# VU.net
KiCad netlist of a schematic drawn in EAGLE
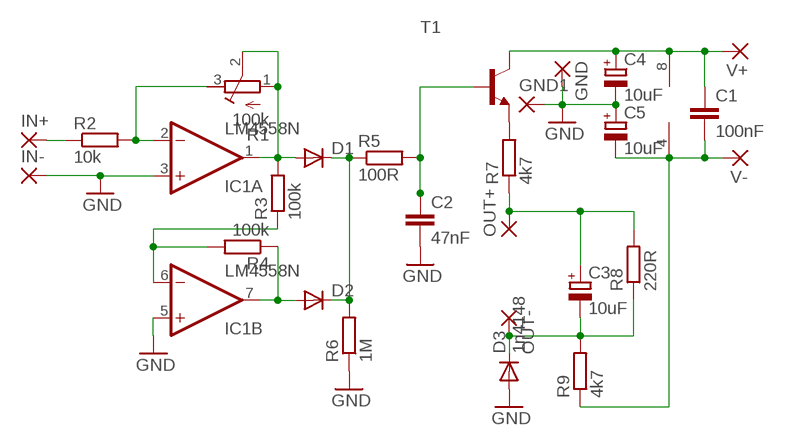
[diagram p0: schematic, sheet 1]

(export (version "E")
  (design (tool "Eeschema 10.0.6"))
  (components
    (comp (ref "C1")
      (value "100nF")
      (footprint "eagle-import:C050-025X075")
      (libsource (lib "eagle-import") (part "C-EU050-025X075"))
    )
    (comp (ref "C2")
      (value "47nF")
      (footprint "eagle-import:C050-025X075")
      (libsource (lib "eagle-import") (part "C-EU050-025X075"))
    )
    (comp (ref "C3")
      (value "10uF")
      (footprint "eagle-import:E2,5-5")
      (libsource (lib "eagle-import") (part "CPOL-EUE2.5-5"))
    )
    (comp (ref "C4")
      (value "10uF")
      (footprint "eagle-import:E2,5-5")
      (libsource (lib "eagle-import") (part "CPOL-EUE2.5-5"))
    )
    (comp (ref "C5")
      (value "10uF")
      (footprint "eagle-import:E2,5-5")
      (libsource (lib "eagle-import") (part "CPOL-EUE2.5-5"))
    )
    (comp (ref "D1")
      (value "DIODE-D-5")
      (footprint "eagle-import:D-5")
      (libsource (lib "eagle-import") (part "DIODE-D-5"))
    )
    (comp (ref "D2")
      (value "DIODE-D-5")
      (footprint "eagle-import:D-5")
      (libsource (lib "eagle-import") (part "DIODE-D-5"))
    )
    (comp (ref "D3")
      (value "1n4148")
      (footprint "eagle-import:D-5")
      (libsource (lib "eagle-import") (part "DIODE-D-5"))
    )
    (comp (ref "GND")
      (value "WIREPAD1,6/0,8")
      (footprint "eagle-import:1,6_0,8")
      (libsource (lib "eagle-import") (part "WIREPAD1,6/0,8"))
    )
    (comp (ref "GND1")
      (value "WIREPAD1,6/0,8")
      (footprint "eagle-import:1,6_0,8")
      (libsource (lib "eagle-import") (part "WIREPAD1,6/0,8"))
    )
    (comp (ref "IC1")
      (value "LM4558N")
      (footprint "eagle-import:DIL08")
      (libsource (lib "eagle-import") (part "4558NLM"))
    )
    (comp (ref "IN+")
      (value "WIREPAD1,6/0,8")
      (footprint "eagle-import:1,6_0,8")
      (libsource (lib "eagle-import") (part "WIREPAD1,6/0,8"))
    )
    (comp (ref "IN-")
      (value "WIREPAD1,6/0,8")
      (footprint "eagle-import:1,6_0,8")
      (libsource (lib "eagle-import") (part "WIREPAD1,6/0,8"))
    )
    (comp (ref "OUT+")
      (value "WIREPAD1,6/0,8")
      (footprint "eagle-import:1,6_0,8")
      (libsource (lib "eagle-import") (part "WIREPAD1,6/0,8"))
    )
    (comp (ref "OUT-")
      (value "WIREPAD1,6/0,8")
      (footprint "eagle-import:1,6_0,8")
      (libsource (lib "eagle-import") (part "WIREPAD1,6/0,8"))
    )
    (comp (ref "R1")
      (value "100k")
      (footprint "eagle-import:RTRIM64X")
      (libsource (lib "eagle-import") (part "R-TRIMM64X"))
    )
    (comp (ref "R2")
      (value "10k")
      (footprint "eagle-import:0207_7")
      (libsource (lib "eagle-import") (part "R-EU_0207/7"))
    )
    (comp (ref "R3")
      (value "100k")
      (footprint "eagle-import:0207_7")
      (libsource (lib "eagle-import") (part "R-EU_0207/7"))
    )
    (comp (ref "R4")
      (value "100k")
      (footprint "eagle-import:0207_2V")
      (libsource (lib "eagle-import") (part "R-EU_0207/2V"))
    )
    (comp (ref "R5")
      (value "100R")
      (footprint "eagle-import:0207_7")
      (libsource (lib "eagle-import") (part "R-EU_0207/7"))
    )
    (comp (ref "R6")
      (value "1M")
      (footprint "eagle-import:0207_7")
      (libsource (lib "eagle-import") (part "R-EU_0207/7"))
    )
    (comp (ref "R7")
      (value "4k7")
      (footprint "eagle-import:0207_7")
      (libsource (lib "eagle-import") (part "R-EU_0207/7"))
    )
    (comp (ref "R8")
      (value "220R")
      (footprint "eagle-import:0207_7")
      (libsource (lib "eagle-import") (part "R-EU_0207/7"))
    )
    (comp (ref "R9")
      (value "4k7")
      (footprint "eagle-import:0207_7")
      (libsource (lib "eagle-import") (part "R-EU_0207/7"))
    )
    (comp (ref "T1")
      (value "BC546-NPN-TO92-CBE")
      (footprint "eagle-import:TO92-CBE")
      (libsource (lib "eagle-import") (part "-NPN-TO92-CBEBC546"))
    )
    (comp (ref "V+")
      (value "WIREPAD1,6/0,8")
      (footprint "eagle-import:1,6_0,8")
      (libsource (lib "eagle-import") (part "WIREPAD1,6/0,8"))
    )
    (comp (ref "V-")
      (value "WIREPAD1,6/0,8")
      (footprint "eagle-import:1,6_0,8")
      (libsource (lib "eagle-import") (part "WIREPAD1,6/0,8"))
    )
  )
  (nets
    (net (code "1") (name "GND") (class "Default")
      (node (ref "C2") (pin "2") (pinfunction "2_2") (pintype "passive"))
      (node (ref "C4") (pin "-") (pinfunction "-_-") (pintype "passive"))
      (node (ref "C5") (pin "+") (pinfunction "+_+") (pintype "passive"))
      (node (ref "D3") (pin "A") (pinfunction "A_A") (pintype "passive"))
      (node (ref "GND") (pin "1") (pinfunction "P_1") (pintype "passive"))
      (node (ref "GND1") (pin "1") (pinfunction "P_1") (pintype "passive"))
      (node (ref "IC1") (pin "3") (pinfunction "+IN_3") (pintype "input"))
      (node (ref "IC1") (pin "5") (pinfunction "+IN_5") (pintype "input"))
      (node (ref "IN-") (pin "1") (pinfunction "P_1") (pintype "passive"))
      (node (ref "R6") (pin "1") (pinfunction "1_1") (pintype "passive"))
    )
    (net (code "2") (name "Net-(C2-Pad1)") (class "Default")
      (node (ref "C2") (pin "1") (pinfunction "1_1") (pintype "passive"))
      (node (ref "R5") (pin "2") (pinfunction "2_2") (pintype "passive"))
      (node (ref "T1") (pin "B") (pinfunction "B_B") (pintype "passive"))
    )
    (net (code "3") (name "Net-(D1-PadC)") (class "Default")
      (node (ref "D1") (pin "C") (pinfunction "C_C") (pintype "passive"))
      (node (ref "D2") (pin "C") (pinfunction "C_C") (pintype "passive"))
      (node (ref "R5") (pin "1") (pinfunction "1_1") (pintype "passive"))
      (node (ref "R6") (pin "2") (pinfunction "2_2") (pintype "passive"))
    )
    (net (code "4") (name "Net-(IC1A--IN)") (class "Default")
      (node (ref "IC1") (pin "2") (pinfunction "-IN_2") (pintype "input"))
      (node (ref "R1") (pin "3") (pinfunction "E_3") (pintype "passive"))
      (node (ref "R2") (pin "2") (pinfunction "2_2") (pintype "passive"))
    )
    (net (code "5") (name "Net-(IC1A-OUT)") (class "Default")
      (node (ref "D1") (pin "A") (pinfunction "A_A") (pintype "passive"))
      (node (ref "IC1") (pin "1") (pinfunction "OUT_1") (pintype "output"))
      (node (ref "R1") (pin "1") (pinfunction "A_1") (pintype "passive"))
      (node (ref "R1") (pin "2") (pinfunction "S_2") (pintype "passive"))
      (node (ref "R3") (pin "2") (pinfunction "2_2") (pintype "passive"))
    )
    (net (code "6") (name "Net-(IC1B--IN)") (class "Default")
      (node (ref "IC1") (pin "6") (pinfunction "-IN_6") (pintype "input"))
      (node (ref "R3") (pin "1") (pinfunction "1_1") (pintype "passive"))
      (node (ref "R4") (pin "2") (pinfunction "2_2") (pintype "passive"))
    )
    (net (code "7") (name "Net-(IC1B-OUT)") (class "Default")
      (node (ref "D2") (pin "A") (pinfunction "A_A") (pintype "passive"))
      (node (ref "IC1") (pin "7") (pinfunction "OUT_7") (pintype "output"))
      (node (ref "R4") (pin "1") (pinfunction "1_1") (pintype "passive"))
    )
    (net (code "8") (name "Net-(IC1C-V+)") (class "Default")
      (node (ref "C1") (pin "1") (pinfunction "1_1") (pintype "passive"))
      (node (ref "C4") (pin "+") (pinfunction "+_+") (pintype "passive"))
      (node (ref "IC1") (pin "8") (pinfunction "V+_8") (pintype "power_in"))
      (node (ref "T1") (pin "C") (pinfunction "C_C") (pintype "passive"))
      (node (ref "V+") (pin "1") (pinfunction "P_1") (pintype "passive"))
    )
    (net (code "9") (name "Net-(IC1C-V-)") (class "Default")
      (node (ref "C1") (pin "2") (pinfunction "2_2") (pintype "passive"))
      (node (ref "C5") (pin "-") (pinfunction "-_-") (pintype "passive"))
      (node (ref "IC1") (pin "4") (pinfunction "V-_4") (pintype "power_in"))
      (node (ref "R9") (pin "1") (pinfunction "1_1") (pintype "passive"))
      (node (ref "V-") (pin "1") (pinfunction "P_1") (pintype "passive"))
    )
    (net (code "10") (name "Net-(IN+-P)") (class "Default")
      (node (ref "IN+") (pin "1") (pinfunction "P_1") (pintype "passive"))
      (node (ref "R2") (pin "1") (pinfunction "1_1") (pintype "passive"))
    )
    (net (code "11") (name "Net-(OUT+-P)") (class "Default")
      (node (ref "C3") (pin "+") (pinfunction "+_+") (pintype "passive"))
      (node (ref "OUT+") (pin "1") (pinfunction "P_1") (pintype "passive"))
      (node (ref "R7") (pin "1") (pinfunction "1_1") (pintype "passive"))
      (node (ref "R8") (pin "2") (pinfunction "2_2") (pintype "passive"))
    )
    (net (code "12") (name "Net-(OUT--P)") (class "Default")
      (node (ref "C3") (pin "-") (pinfunction "-_-") (pintype "passive"))
      (node (ref "D3") (pin "C") (pinfunction "C_C") (pintype "passive"))
      (node (ref "OUT-") (pin "1") (pinfunction "P_1") (pintype "passive"))
      (node (ref "R8") (pin "1") (pinfunction "1_1") (pintype "passive"))
      (node (ref "R9") (pin "2") (pinfunction "2_2") (pintype "passive"))
    )
    (net (code "13") (name "Net-(R7-Pad2)") (class "Default")
      (node (ref "R7") (pin "2") (pinfunction "2_2") (pintype "passive"))
      (node (ref "T1") (pin "E") (pinfunction "E_E") (pintype "passive"))
    )
  )
)
